# C64_Kernal_Switch.net
KiCad netlist of a schematic drawn in EAGLE
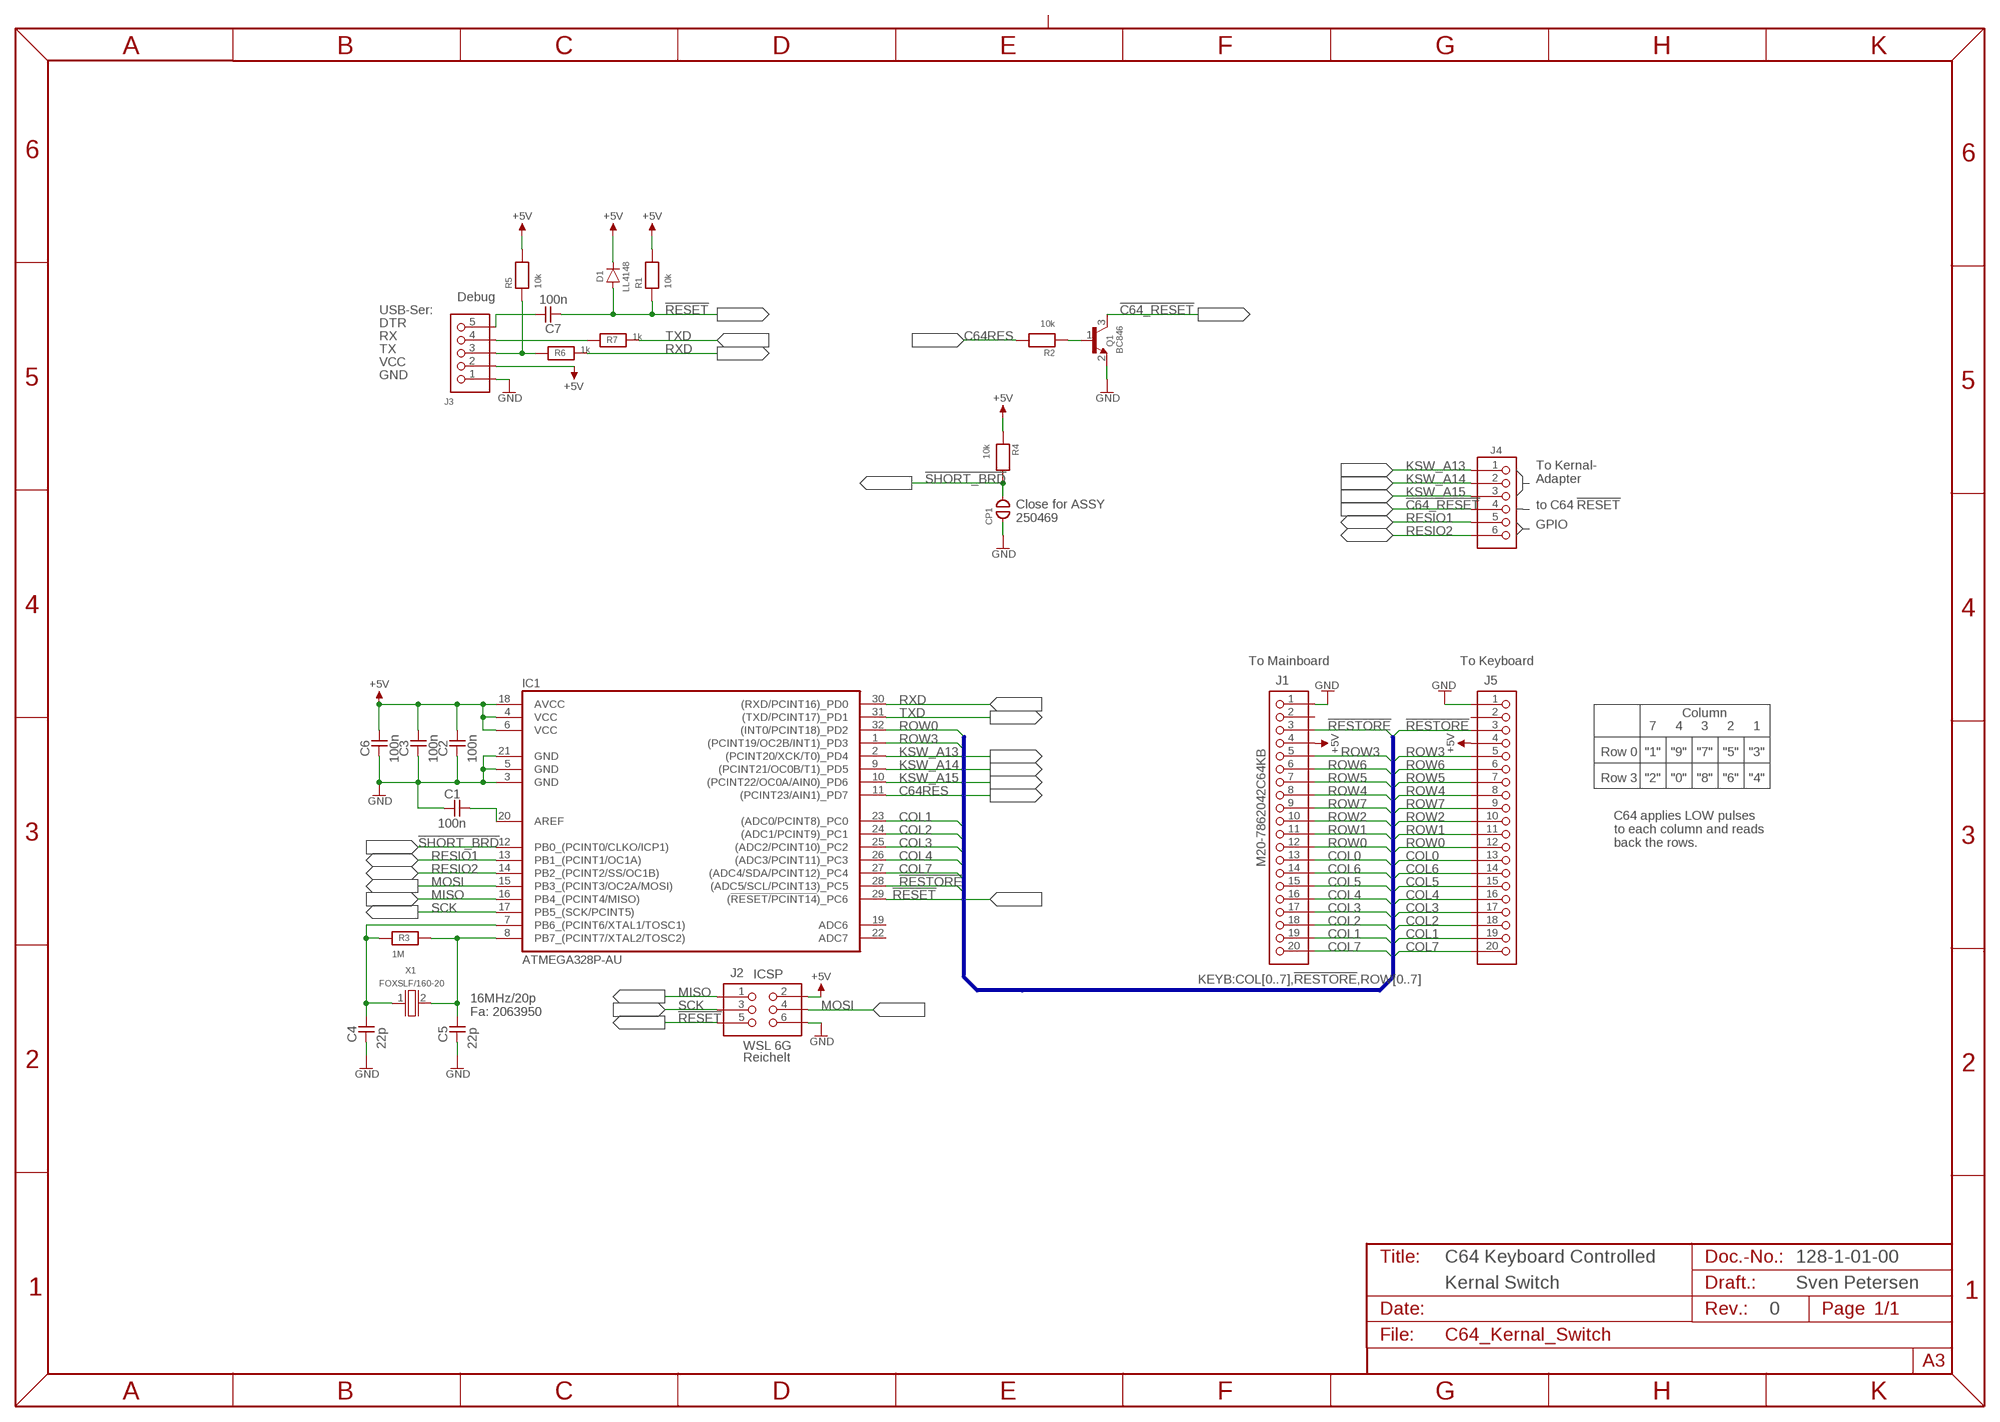
[diagram p0: schematic, sheet 1]

(export (version "E")
  (design (tool "Eeschema 10.0.6"))
  (components
    (comp (ref "C1")
      (value "100n")
      (footprint "eagle-import:0805")
      (libsource (lib "eagle-import") (part "C-0805"))
    )
    (comp (ref "C2")
      (value "100n")
      (footprint "eagle-import:0805")
      (libsource (lib "eagle-import") (part "C-0805"))
    )
    (comp (ref "C3")
      (value "100n")
      (footprint "eagle-import:0805")
      (libsource (lib "eagle-import") (part "C-0805"))
    )
    (comp (ref "C4")
      (value "22p")
      (footprint "eagle-import:0805")
      (libsource (lib "eagle-import") (part "C-0805"))
    )
    (comp (ref "C5")
      (value "22p")
      (footprint "eagle-import:0805")
      (libsource (lib "eagle-import") (part "C-0805"))
    )
    (comp (ref "C6")
      (value "100n")
      (footprint "eagle-import:0805")
      (libsource (lib "eagle-import") (part "C-0805"))
    )
    (comp (ref "C7")
      (value "100n")
      (footprint "eagle-import:0805")
      (libsource (lib "eagle-import") (part "C-0805"))
    )
    (comp (ref "CP1")
      (value "OPEN")
      (footprint "eagle-import:CP_OP")
      (libsource (lib "eagle-import") (part "OPEN"))
    )
    (comp (ref "D1")
      (value "LL4148")
      (footprint "eagle-import:SOD80C")
      (libsource (lib "eagle-import") (part "LL4148"))
    )
    (comp (ref "IC1")
      (value "ATMEGA328P-AU")
      (footprint "eagle-import:QFP80P900X900X120-32N")
      (fields (field (name "MPN") "ATMEGA328-AU"))
      (libsource (lib "eagle-import") (part "ATMEGA328-AU"))
    )
    (comp (ref "J1")
      (value "M20-7862042C64KB")
      (footprint "eagle-import:C64_KEYBOARD")
      (fields (field (name "SPICEPREFIX") "X"))
      (libsource (lib "eagle-import") (part "M20-7862042C64KB"))
    )
    (comp (ref "J2")
      (value "WSL 6G")
      (footprint "eagle-import:2X03WV")
      (libsource (lib "eagle-import") (part "2X03WV"))
    )
    (comp (ref "J3")
      (value "n/a")
      (footprint "eagle-import:1X05")
      (libsource (lib "eagle-import") (part "PINHD-1X5"))
    )
    (comp (ref "J4")
      (value "PINHD-1X6")
      (footprint "eagle-import:1X06")
      (libsource (lib "eagle-import") (part "PINHD-1X6"))
    )
    (comp (ref "J5")
      (value "PINHD-1X20")
      (footprint "eagle-import:1X20")
      (libsource (lib "eagle-import") (part "PINHD-1X20"))
    )
    (comp (ref "Q1")
      (value "BC846")
      (footprint "eagle-import:SOT23")
      (libsource (lib "eagle-import") (part "BC846"))
    )
    (comp (ref "R1")
      (value "10k")
      (footprint "eagle-import:0805")
      (libsource (lib "eagle-import") (part "R-0805"))
    )
    (comp (ref "R2")
      (value "10k")
      (footprint "eagle-import:0805")
      (libsource (lib "eagle-import") (part "R-0805"))
    )
    (comp (ref "R3")
      (value "1M")
      (footprint "eagle-import:0805")
      (libsource (lib "eagle-import") (part "R-0805"))
    )
    (comp (ref "R4")
      (value "10k")
      (footprint "eagle-import:0805")
      (libsource (lib "eagle-import") (part "R-0805"))
    )
    (comp (ref "R5")
      (value "10k")
      (footprint "eagle-import:0805")
      (libsource (lib "eagle-import") (part "R-0805"))
    )
    (comp (ref "R6")
      (value "1k")
      (footprint "eagle-import:0805")
      (libsource (lib "eagle-import") (part "R-0805"))
    )
    (comp (ref "R7")
      (value "1k")
      (footprint "eagle-import:0805")
      (libsource (lib "eagle-import") (part "R-0805"))
    )
    (comp (ref "X1")
      (value "FOXSLF/160-20")
      (footprint "eagle-import:HC49SLF")
      (libsource (lib "eagle-import") (part "HC49SLF"))
    )
  )
  (nets
    (net (code "1") (name "+5V") (class "Default")
      (node (ref "C2") (pin "2") (pinfunction "2_2") (pintype "passive"))
      (node (ref "C3") (pin "2") (pinfunction "2_2") (pintype "passive"))
      (node (ref "C6") (pin "2") (pinfunction "2_2") (pintype "passive"))
      (node (ref "D1") (pin "K") (pinfunction "K_K") (pintype "passive"))
      (node (ref "IC1") (pin "18") (pinfunction "AVCC_18") (pintype "power_in"))
      (node (ref "IC1") (pin "4") (pinfunction "VCC_4") (pintype "power_in"))
      (node (ref "IC1") (pin "6") (pinfunction "VCC_6") (pintype "power_in"))
      (node (ref "J1") (pin "4") (pinfunction "4_4") (pintype "bidirectional"))
      (node (ref "J2") (pin "2") (pinfunction "2_2") (pintype "passive"))
      (node (ref "J3") (pin "2") (pinfunction "2_2") (pintype "passive"))
      (node (ref "J5") (pin "4") (pinfunction "4_4") (pintype "passive"))
      (node (ref "R1") (pin "2") (pinfunction "2_2") (pintype "passive"))
      (node (ref "R4") (pin "1") (pinfunction "1_1") (pintype "passive"))
      (node (ref "R5") (pin "2") (pinfunction "2_2") (pintype "passive"))
    )
    (net (code "2") (name "/C64RES") (class "Default")
      (node (ref "IC1") (pin "11") (pinfunction "(PCINT23/AIN1)_PD7_11") (pintype "bidirectional"))
      (node (ref "R2") (pin "2") (pinfunction "2_2") (pintype "passive"))
    )
    (net (code "3") (name "/COL0") (class "Default")
      (node (ref "J1") (pin "13") (pinfunction "13_13") (pintype "bidirectional"))
      (node (ref "J5") (pin "13") (pinfunction "13_13") (pintype "passive"))
    )
    (net (code "4") (name "/COL1") (class "Default")
      (node (ref "IC1") (pin "23") (pinfunction "(ADC0/PCINT8)_PC0_23") (pintype "bidirectional"))
      (node (ref "J1") (pin "19") (pinfunction "19_19") (pintype "bidirectional"))
      (node (ref "J5") (pin "19") (pinfunction "19_19") (pintype "passive"))
    )
    (net (code "5") (name "/COL2") (class "Default")
      (node (ref "IC1") (pin "24") (pinfunction "(ADC1/PCINT9)_PC1_24") (pintype "bidirectional"))
      (node (ref "J1") (pin "18") (pinfunction "18_18") (pintype "bidirectional"))
      (node (ref "J5") (pin "18") (pinfunction "18_18") (pintype "passive"))
    )
    (net (code "6") (name "/COL3") (class "Default")
      (node (ref "IC1") (pin "25") (pinfunction "(ADC2/PCINT10)_PC2_25") (pintype "bidirectional"))
      (node (ref "J1") (pin "17") (pinfunction "17_17") (pintype "bidirectional"))
      (node (ref "J5") (pin "17") (pinfunction "17_17") (pintype "passive"))
    )
    (net (code "7") (name "/COL4") (class "Default")
      (node (ref "IC1") (pin "26") (pinfunction "(ADC3/PCINT11)_PC3_26") (pintype "bidirectional"))
      (node (ref "J1") (pin "16") (pinfunction "16_16") (pintype "bidirectional"))
      (node (ref "J5") (pin "16") (pinfunction "16_16") (pintype "passive"))
    )
    (net (code "8") (name "/COL5") (class "Default")
      (node (ref "J1") (pin "15") (pinfunction "15_15") (pintype "bidirectional"))
      (node (ref "J5") (pin "15") (pinfunction "15_15") (pintype "passive"))
    )
    (net (code "9") (name "/COL6") (class "Default")
      (node (ref "J1") (pin "14") (pinfunction "14_14") (pintype "bidirectional"))
      (node (ref "J5") (pin "14") (pinfunction "14_14") (pintype "passive"))
    )
    (net (code "10") (name "/COL7") (class "Default")
      (node (ref "IC1") (pin "27") (pinfunction "(ADC4/SDA/PCINT12)_PC4_27") (pintype "bidirectional"))
      (node (ref "J1") (pin "20") (pinfunction "20_20") (pintype "bidirectional"))
      (node (ref "J5") (pin "20") (pinfunction "20_20") (pintype "passive"))
    )
    (net (code "11") (name "/KSW_A13") (class "Default")
      (node (ref "IC1") (pin "2") (pinfunction "(PCINT20/XCK/T0)_PD4_2") (pintype "bidirectional"))
      (node (ref "J4") (pin "1") (pinfunction "1_1") (pintype "passive"))
    )
    (net (code "12") (name "/KSW_A14") (class "Default")
      (node (ref "IC1") (pin "9") (pinfunction "(PCINT21/OC0B/T1)_PD5_9") (pintype "bidirectional"))
      (node (ref "J4") (pin "2") (pinfunction "2_2") (pintype "passive"))
    )
    (net (code "13") (name "/KSW_A15") (class "Default")
      (node (ref "IC1") (pin "10") (pinfunction "(PCINT22/OC0A/AIN0)_PD6_10") (pintype "bidirectional"))
      (node (ref "J4") (pin "3") (pinfunction "3_3") (pintype "passive"))
    )
    (net (code "14") (name "/MISO") (class "Default")
      (node (ref "IC1") (pin "16") (pinfunction "PB4_(PCINT4/MISO)_16") (pintype "bidirectional"))
      (node (ref "J2") (pin "1") (pinfunction "1_1") (pintype "passive"))
    )
    (net (code "15") (name "/MOSI") (class "Default")
      (node (ref "IC1") (pin "15") (pinfunction "PB3_(PCINT3/OC2A/MOSI)_15") (pintype "bidirectional"))
      (node (ref "J2") (pin "4") (pinfunction "4_4") (pintype "passive"))
    )
    (net (code "16") (name "/RESIO1") (class "Default")
      (node (ref "IC1") (pin "13") (pinfunction "PB1_(PCINT1/OC1A)_13") (pintype "bidirectional"))
      (node (ref "J4") (pin "5") (pinfunction "5_5") (pintype "passive"))
    )
    (net (code "17") (name "/RESIO2") (class "Default")
      (node (ref "IC1") (pin "14") (pinfunction "PB2_(PCINT2/SS/OC1B)_14") (pintype "bidirectional"))
      (node (ref "J4") (pin "6") (pinfunction "6_6") (pintype "passive"))
    )
    (net (code "18") (name "/ROW0") (class "Default")
      (node (ref "IC1") (pin "32") (pinfunction "(INT0/PCINT18)_PD2_32") (pintype "bidirectional"))
      (node (ref "J1") (pin "12") (pinfunction "12_12") (pintype "bidirectional"))
      (node (ref "J5") (pin "12") (pinfunction "12_12") (pintype "passive"))
    )
    (net (code "19") (name "/ROW1") (class "Default")
      (node (ref "J1") (pin "11") (pinfunction "11_11") (pintype "bidirectional"))
      (node (ref "J5") (pin "11") (pinfunction "11_11") (pintype "passive"))
    )
    (net (code "20") (name "/ROW2") (class "Default")
      (node (ref "J1") (pin "10") (pinfunction "10_10") (pintype "bidirectional"))
      (node (ref "J5") (pin "10") (pinfunction "10_10") (pintype "passive"))
    )
    (net (code "21") (name "/ROW3") (class "Default")
      (node (ref "IC1") (pin "1") (pinfunction "(PCINT19/OC2B/INT1)_PD3_1") (pintype "bidirectional"))
      (node (ref "J1") (pin "5") (pinfunction "5_5") (pintype "bidirectional"))
      (node (ref "J5") (pin "5") (pinfunction "5_5") (pintype "passive"))
    )
    (net (code "22") (name "/ROW4") (class "Default")
      (node (ref "J1") (pin "8") (pinfunction "8_8") (pintype "bidirectional"))
      (node (ref "J5") (pin "8") (pinfunction "8_8") (pintype "passive"))
    )
    (net (code "23") (name "/ROW5") (class "Default")
      (node (ref "J1") (pin "7") (pinfunction "7_7") (pintype "bidirectional"))
      (node (ref "J5") (pin "7") (pinfunction "7_7") (pintype "passive"))
    )
    (net (code "24") (name "/ROW6") (class "Default")
      (node (ref "J1") (pin "6") (pinfunction "6_6") (pintype "bidirectional"))
      (node (ref "J5") (pin "6") (pinfunction "6_6") (pintype "passive"))
    )
    (net (code "25") (name "/ROW7") (class "Default")
      (node (ref "J1") (pin "9") (pinfunction "9_9") (pintype "bidirectional"))
      (node (ref "J5") (pin "9") (pinfunction "9_9") (pintype "passive"))
    )
    (net (code "26") (name "/RXD") (class "Default")
      (node (ref "IC1") (pin "30") (pinfunction "(RXD/PCINT16)_PD0_30") (pintype "bidirectional"))
      (node (ref "R6") (pin "2") (pinfunction "2_2") (pintype "passive"))
    )
    (net (code "27") (name "/SCK") (class "Default")
      (node (ref "IC1") (pin "17") (pinfunction "PB5_(SCK/PCINT5)_17") (pintype "bidirectional"))
      (node (ref "J2") (pin "3") (pinfunction "3_3") (pintype "passive"))
    )
    (net (code "28") (name "/TXD") (class "Default")
      (node (ref "IC1") (pin "31") (pinfunction "(TXD/PCINT17)_PD1_31") (pintype "bidirectional"))
      (node (ref "R7") (pin "2") (pinfunction "2_2") (pintype "passive"))
    )
    (net (code "30") (name "/~{C64_RESET}") (class "Default")
      (node (ref "J4") (pin "4") (pinfunction "4_4") (pintype "passive"))
      (node (ref "Q1") (pin "3") (pinfunction "C_3") (pintype "passive"))
    )
    (net (code "31") (name "/~{RESET}") (class "Default")
      (node (ref "C7") (pin "1") (pinfunction "1_1") (pintype "passive"))
      (node (ref "D1") (pin "A") (pinfunction "A_A") (pintype "passive"))
      (node (ref "IC1") (pin "29") (pinfunction "(~{RESET/PCINT14})_PC6_29") (pintype "bidirectional"))
      (node (ref "J2") (pin "5") (pinfunction "5_5") (pintype "passive"))
      (node (ref "R1") (pin "1") (pinfunction "1_1") (pintype "passive"))
    )
    (net (code "32") (name "/~{RESTORE}") (class "Default")
      (node (ref "IC1") (pin "28") (pinfunction "(ADC5/SCL/PCINT13)_PC5_28") (pintype "bidirectional"))
      (node (ref "J1") (pin "3") (pinfunction "3_3") (pintype "bidirectional"))
      (node (ref "J5") (pin "3") (pinfunction "3_3") (pintype "passive"))
    )
    (net (code "33") (name "/~{SHORT_BRD}") (class "Default")
      (node (ref "CP1") (pin "2") (pinfunction "2_2") (pintype "passive"))
      (node (ref "IC1") (pin "12") (pinfunction "PB0_(PCINT0/CLKO/ICP1)_12") (pintype "bidirectional"))
      (node (ref "R4") (pin "2") (pinfunction "2_2") (pintype "passive"))
    )
    (net (code "34") (name "GND") (class "Default")
      (node (ref "C1") (pin "1") (pinfunction "1_1") (pintype "passive"))
      (node (ref "C2") (pin "1") (pinfunction "1_1") (pintype "passive"))
      (node (ref "C3") (pin "1") (pinfunction "1_1") (pintype "passive"))
      (node (ref "C4") (pin "1") (pinfunction "1_1") (pintype "passive"))
      (node (ref "C5") (pin "1") (pinfunction "1_1") (pintype "passive"))
      (node (ref "C6") (pin "1") (pinfunction "1_1") (pintype "passive"))
      (node (ref "CP1") (pin "1") (pinfunction "1_1") (pintype "passive"))
      (node (ref "IC1") (pin "21") (pinfunction "GND_21") (pintype "passive"))
      (node (ref "IC1") (pin "3") (pinfunction "GND_3") (pintype "passive"))
      (node (ref "IC1") (pin "5") (pinfunction "GND_5") (pintype "passive"))
      (node (ref "J1") (pin "1") (pinfunction "1_1") (pintype "bidirectional"))
      (node (ref "J2") (pin "6") (pinfunction "6_6") (pintype "passive"))
      (node (ref "J3") (pin "1") (pinfunction "1_1") (pintype "passive"))
      (node (ref "J5") (pin "1") (pinfunction "1_1") (pintype "passive"))
      (node (ref "Q1") (pin "2") (pinfunction "E_2") (pintype "passive"))
    )
    (net (code "35") (name "Net-(C7-Pad2)") (class "Default")
      (node (ref "C7") (pin "2") (pinfunction "2_2") (pintype "passive"))
      (node (ref "J3") (pin "5") (pinfunction "5_5") (pintype "passive"))
    )
    (net (code "36") (name "Net-(IC1-AREF)") (class "Default")
      (node (ref "C1") (pin "2") (pinfunction "2_2") (pintype "passive"))
      (node (ref "IC1") (pin "20") (pinfunction "AREF_20") (pintype "passive"))
    )
    (net (code "37") (name "Net-(IC1-PB6_(PCINT6{slash}XTAL1{slash}TOSC1))") (class "Default")
      (node (ref "C4") (pin "2") (pinfunction "2_2") (pintype "passive"))
      (node (ref "IC1") (pin "7") (pinfunction "PB6_(PCINT6/XTAL1/TOSC1)_7") (pintype "bidirectional"))
      (node (ref "R3") (pin "1") (pinfunction "1_1") (pintype "passive"))
      (node (ref "X1") (pin "1") (pinfunction "1_1") (pintype "passive"))
    )
    (net (code "38") (name "Net-(IC1-PB7_(PCINT7{slash}XTAL2{slash}TOSC2))") (class "Default")
      (node (ref "C5") (pin "2") (pinfunction "2_2") (pintype "passive"))
      (node (ref "IC1") (pin "8") (pinfunction "PB7_(PCINT7/XTAL2/TOSC2)_8") (pintype "bidirectional"))
      (node (ref "R3") (pin "2") (pinfunction "2_2") (pintype "passive"))
      (node (ref "X1") (pin "2") (pinfunction "2_2") (pintype "passive"))
    )
    (net (code "39") (name "Net-(J3-Pad3)") (class "Default")
      (node (ref "J3") (pin "3") (pinfunction "3_3") (pintype "passive"))
      (node (ref "R5") (pin "1") (pinfunction "1_1") (pintype "passive"))
      (node (ref "R6") (pin "1") (pinfunction "1_1") (pintype "passive"))
    )
    (net (code "40") (name "Net-(J3-Pad4)") (class "Default")
      (node (ref "J3") (pin "4") (pinfunction "4_4") (pintype "passive"))
      (node (ref "R7") (pin "1") (pinfunction "1_1") (pintype "passive"))
    )
    (net (code "41") (name "Net-(Q1-B)") (class "Default")
      (node (ref "Q1") (pin "1") (pinfunction "B_1") (pintype "passive"))
      (node (ref "R2") (pin "1") (pinfunction "1_1") (pintype "passive"))
    )
    (net (code "42") (name "unconnected-(IC1-ADC6-Pad19)") (class "Default")
      (node (ref "IC1") (pin "19") (pinfunction "ADC6_19") (pintype "input"))
    )
    (net (code "43") (name "unconnected-(IC1-ADC7-Pad22)") (class "Default")
      (node (ref "IC1") (pin "22") (pinfunction "ADC7_22") (pintype "input"))
    )
    (net (code "44") (name "unconnected-(J1-Pad2)") (class "Default")
      (node (ref "J1") (pin "2") (pinfunction "2_2") (pintype "bidirectional"))
    )
    (net (code "45") (name "unconnected-(J5-Pad2)") (class "Default")
      (node (ref "J5") (pin "2") (pinfunction "2_2") (pintype "passive"))
    )
  )
)
